# Lego_PowerFunctions_I2C_Board.net
KiCad netlist of a schematic drawn in EAGLE
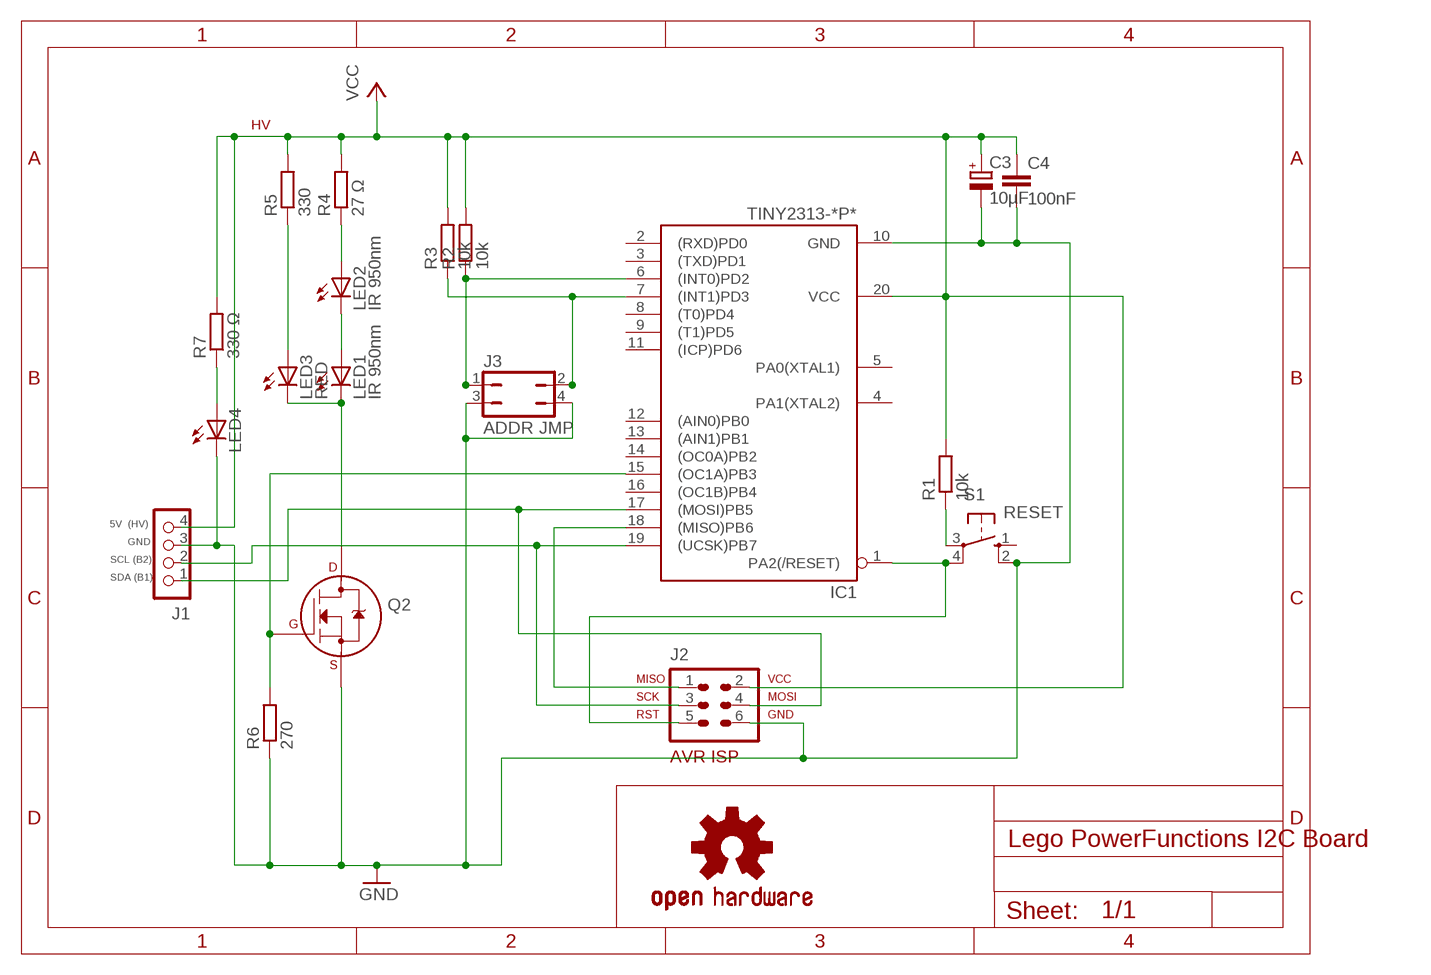
[diagram p0: schematic, sheet 1]

(export (version "E")
  (design (tool "Eeschema 10.0.6"))
  (components
    (comp (ref "C3")
      (value "10µF")
      (footprint "eagle-import:E2,5-6")
      (libsource (lib "eagle-import") (part "CPOL-EUE2.5-6"))
    )
    (comp (ref "C4")
      (value "100nF")
      (footprint "eagle-import:C025-025X050")
      (libsource (lib "eagle-import") (part "C-EU025-025X050"))
    )
    (comp (ref "IC1")
      (value "TINY2313-*P*")
      (footprint "eagle-import:DIL20")
      (libsource (lib "eagle-import") (part "TINY2313-P"))
    )
    (comp (ref "J1")
      (value "CON_HEADER_1X04")
      (footprint "eagle-import:M1X4")
      (libsource (lib "eagle-import") (part "CON_HEADER_1X04"))
    )
    (comp (ref "J2")
      (value "AVR-ISP-6VERT")
      (footprint "eagle-import:AVR-ISP-6")
      (libsource (lib "eagle-import") (part "AVR-ISP-6VERT"))
    )
    (comp (ref "J3")
      (value "ADDR JMP")
      (footprint "eagle-import:JP2Q")
      (libsource (lib "eagle-import") (part "JP2Q"))
    )
    (comp (ref "LED1")
      (value "IR 950nm")
      (footprint "eagle-import:LED5MM")
      (libsource (lib "eagle-import") (part "LED5MM"))
    )
    (comp (ref "LED2")
      (value "IR 950nm")
      (footprint "eagle-import:LED5MM")
      (libsource (lib "eagle-import") (part "LED5MM"))
    )
    (comp (ref "LED3")
      (value "RED")
      (footprint "eagle-import:LED3MM")
      (libsource (lib "eagle-import") (part "LED3MM"))
    )
    (comp (ref "LED4")
      (value "LED3MM")
      (footprint "eagle-import:LED3MM")
      (libsource (lib "eagle-import") (part "LED3MM"))
    )
    (comp (ref "LOGO1")
      (value "OSHW-LOGOM")
      (footprint "eagle-import:OSHW-LOGO-M")
      (libsource (lib "eagle-import") (part "OSHW-LOGOM"))
    )
    (comp (ref "Q2")
      (value "2N7000_TO92")
      (footprint "eagle-import:TO-92")
      (libsource (lib "eagle-import") (part "2N700_TO920"))
    )
    (comp (ref "R1")
      (value "10k")
      (footprint "eagle-import:0207_10")
      (libsource (lib "eagle-import") (part "R-EU_0207/10"))
    )
    (comp (ref "R2")
      (value "10k")
      (footprint "eagle-import:0207_10")
      (libsource (lib "eagle-import") (part "R-EU_0207/10"))
    )
    (comp (ref "R3")
      (value "10k")
      (footprint "eagle-import:0207_10")
      (libsource (lib "eagle-import") (part "R-EU_0207/10"))
    )
    (comp (ref "R4")
      (value "27 Ω")
      (footprint "eagle-import:0207_10")
      (libsource (lib "eagle-import") (part "R-EU_0207/10"))
    )
    (comp (ref "R5")
      (value "330")
      (footprint "eagle-import:0207_10")
      (libsource (lib "eagle-import") (part "R-EU_0207/10"))
    )
    (comp (ref "R6")
      (value "270")
      (footprint "eagle-import:0207_10")
      (libsource (lib "eagle-import") (part "R-EU_0207/10"))
    )
    (comp (ref "R7")
      (value "330 Ω")
      (footprint "eagle-import:0207_10")
      (libsource (lib "eagle-import") (part "R-EU_0207/10"))
    )
    (comp (ref "S1")
      (value "RESET")
      (footprint "eagle-import:B3F-10XX")
      (fields (field (name "MPN") "B3F-1000"))
      (libsource (lib "eagle-import") (part "10-XX"))
    )
  )
  (nets
    (net (code "1") (name "GND") (class "Default")
      (node (ref "C3") (pin "-") (pinfunction "-_-") (pintype "passive"))
      (node (ref "C4") (pin "2") (pinfunction "2_2") (pintype "passive"))
      (node (ref "IC1") (pin "10") (pinfunction "GND_10") (pintype "power_in"))
      (node (ref "J1") (pin "3") (pinfunction "3_3") (pintype "bidirectional"))
      (node (ref "J2") (pin "6") (pinfunction "6_6") (pintype "passive"))
      (node (ref "J3") (pin "3") (pinfunction "3_3") (pintype "passive"))
      (node (ref "J3") (pin "4") (pinfunction "4_4") (pintype "passive"))
      (node (ref "LED4") (pin "K") (pinfunction "C_K") (pintype "passive"))
      (node (ref "Q2") (pin "1") (pinfunction "S_1") (pintype "bidirectional"))
      (node (ref "R6") (pin "1") (pinfunction "1_1") (pintype "passive"))
      (node (ref "S1") (pin "2") (pinfunction "S1_2") (pintype "passive"))
    )
    (net (code "2") (name "Net-(IC1-(INT0)PD2)") (class "Default")
      (node (ref "IC1") (pin "6") (pinfunction "(INT0)PD2_6") (pintype "bidirectional"))
      (node (ref "J3") (pin "1") (pinfunction "1_1") (pintype "passive"))
      (node (ref "R2") (pin "1") (pinfunction "1_1") (pintype "passive"))
    )
    (net (code "3") (name "Net-(IC1-(INT1)PD3)") (class "Default")
      (node (ref "IC1") (pin "7") (pinfunction "(INT1)PD3_7") (pintype "bidirectional"))
      (node (ref "J3") (pin "2") (pinfunction "2_2") (pintype "passive"))
      (node (ref "R3") (pin "1") (pinfunction "1_1") (pintype "passive"))
    )
    (net (code "4") (name "Net-(IC1-(MISO)PB6)") (class "Default")
      (node (ref "IC1") (pin "18") (pinfunction "(MISO)PB6_18") (pintype "bidirectional"))
      (node (ref "J2") (pin "1") (pinfunction "1_1") (pintype "passive"))
    )
    (net (code "5") (name "Net-(IC1-(MOSI)PB5)") (class "Default")
      (node (ref "IC1") (pin "17") (pinfunction "(MOSI)PB5_17") (pintype "bidirectional"))
      (node (ref "J1") (pin "1") (pinfunction "1_1") (pintype "bidirectional"))
      (node (ref "J2") (pin "4") (pinfunction "4_4") (pintype "passive"))
    )
    (net (code "6") (name "Net-(IC1-(OC1A)PB3)") (class "Default")
      (node (ref "IC1") (pin "15") (pinfunction "(OC1A)PB3_15") (pintype "bidirectional"))
      (node (ref "Q2") (pin "2") (pinfunction "G_2") (pintype "tri_state"))
      (node (ref "R6") (pin "2") (pinfunction "2_2") (pintype "passive"))
    )
    (net (code "7") (name "Net-(IC1-(UCSK)PB7)") (class "Default")
      (node (ref "IC1") (pin "19") (pinfunction "(UCSK)PB7_19") (pintype "bidirectional"))
      (node (ref "J1") (pin "2") (pinfunction "2_2") (pintype "bidirectional"))
      (node (ref "J2") (pin "3") (pinfunction "3_3") (pintype "passive"))
    )
    (net (code "8") (name "Net-(IC1-PA2({slash}RESET))") (class "Default")
      (node (ref "IC1") (pin "1") (pinfunction "PA2(/RESET)_1") (pintype "input"))
      (node (ref "J2") (pin "5") (pinfunction "5_5") (pintype "passive"))
      (node (ref "S1") (pin "4") (pinfunction "P1_4") (pintype "passive"))
    )
    (net (code "9") (name "Net-(LED1-C)") (class "Default")
      (node (ref "LED1") (pin "K") (pinfunction "C_K") (pintype "passive"))
      (node (ref "LED3") (pin "K") (pinfunction "C_K") (pintype "passive"))
      (node (ref "Q2") (pin "3") (pinfunction "D_3") (pintype "bidirectional"))
    )
    (net (code "10") (name "Net-(LED2-C)") (class "Default")
      (node (ref "LED1") (pin "A") (pinfunction "A_A") (pintype "passive"))
      (node (ref "LED2") (pin "K") (pinfunction "C_K") (pintype "passive"))
    )
    (net (code "11") (name "Net-(LED2-PadA)") (class "Default")
      (node (ref "LED2") (pin "A") (pinfunction "A_A") (pintype "passive"))
      (node (ref "R4") (pin "1") (pinfunction "1_1") (pintype "passive"))
    )
    (net (code "12") (name "Net-(LED3-PadA)") (class "Default")
      (node (ref "LED3") (pin "A") (pinfunction "A_A") (pintype "passive"))
      (node (ref "R5") (pin "1") (pinfunction "1_1") (pintype "passive"))
    )
    (net (code "13") (name "Net-(LED4-PadA)") (class "Default")
      (node (ref "LED4") (pin "A") (pinfunction "A_A") (pintype "passive"))
      (node (ref "R7") (pin "1") (pinfunction "1_1") (pintype "passive"))
    )
    (net (code "14") (name "Net-(S1-P)") (class "Default")
      (node (ref "R1") (pin "1") (pinfunction "1_1") (pintype "passive"))
      (node (ref "S1") (pin "3") (pinfunction "P_3") (pintype "passive"))
    )
    (net (code "15") (name "VCC") (class "Default")
      (node (ref "C3") (pin "+") (pinfunction "+_+") (pintype "passive"))
      (node (ref "C4") (pin "1") (pinfunction "1_1") (pintype "passive"))
      (node (ref "IC1") (pin "20") (pinfunction "VCC_20") (pintype "power_in"))
      (node (ref "J1") (pin "4") (pinfunction "4_4") (pintype "bidirectional"))
      (node (ref "J2") (pin "2") (pinfunction "2_2") (pintype "passive"))
      (node (ref "R1") (pin "2") (pinfunction "2_2") (pintype "passive"))
      (node (ref "R2") (pin "2") (pinfunction "2_2") (pintype "passive"))
      (node (ref "R3") (pin "2") (pinfunction "2_2") (pintype "passive"))
      (node (ref "R4") (pin "2") (pinfunction "2_2") (pintype "passive"))
      (node (ref "R5") (pin "2") (pinfunction "2_2") (pintype "passive"))
      (node (ref "R7") (pin "2") (pinfunction "2_2") (pintype "passive"))
    )
    (net (code "16") (name "unconnected-(IC1-(AIN0)PB0-Pad12)") (class "Default")
      (node (ref "IC1") (pin "12") (pinfunction "(AIN0)PB0_12") (pintype "bidirectional"))
    )
    (net (code "17") (name "unconnected-(IC1-(AIN1)PB1-Pad13)") (class "Default")
      (node (ref "IC1") (pin "13") (pinfunction "(AIN1)PB1_13") (pintype "bidirectional"))
    )
    (net (code "18") (name "unconnected-(IC1-(ICP)PD6-Pad11)") (class "Default")
      (node (ref "IC1") (pin "11") (pinfunction "(ICP)PD6_11") (pintype "bidirectional"))
    )
    (net (code "19") (name "unconnected-(IC1-(OC0A)PB2-Pad14)") (class "Default")
      (node (ref "IC1") (pin "14") (pinfunction "(OC0A)PB2_14") (pintype "bidirectional"))
    )
    (net (code "20") (name "unconnected-(IC1-(OC1B)PB4-Pad16)") (class "Default")
      (node (ref "IC1") (pin "16") (pinfunction "(OC1B)PB4_16") (pintype "bidirectional"))
    )
    (net (code "21") (name "unconnected-(IC1-(RXD)PD0-Pad2)") (class "Default")
      (node (ref "IC1") (pin "2") (pinfunction "(RXD)PD0_2") (pintype "bidirectional"))
    )
    (net (code "22") (name "unconnected-(IC1-(T0)PD4-Pad8)") (class "Default")
      (node (ref "IC1") (pin "8") (pinfunction "(T0)PD4_8") (pintype "bidirectional"))
    )
    (net (code "23") (name "unconnected-(IC1-(T1)PD5-Pad9)") (class "Default")
      (node (ref "IC1") (pin "9") (pinfunction "(T1)PD5_9") (pintype "bidirectional"))
    )
    (net (code "24") (name "unconnected-(IC1-(TXD)PD1-Pad3)") (class "Default")
      (node (ref "IC1") (pin "3") (pinfunction "(TXD)PD1_3") (pintype "bidirectional"))
    )
    (net (code "25") (name "unconnected-(IC1-PA0(XTAL1)-Pad5)") (class "Default")
      (node (ref "IC1") (pin "5") (pinfunction "PA0(XTAL1)_5") (pintype "bidirectional"))
    )
    (net (code "26") (name "unconnected-(IC1-PA1(XTAL2)-Pad4)") (class "Default")
      (node (ref "IC1") (pin "4") (pinfunction "PA1(XTAL2)_4") (pintype "bidirectional"))
    )
    (net (code "27") (name "unconnected-(S1-S-Pad1)") (class "Default")
      (node (ref "S1") (pin "1") (pinfunction "S_1") (pintype "passive"))
    )
  )
)
